# puente.net
KiCad netlist of a schematic drawn in EAGLE
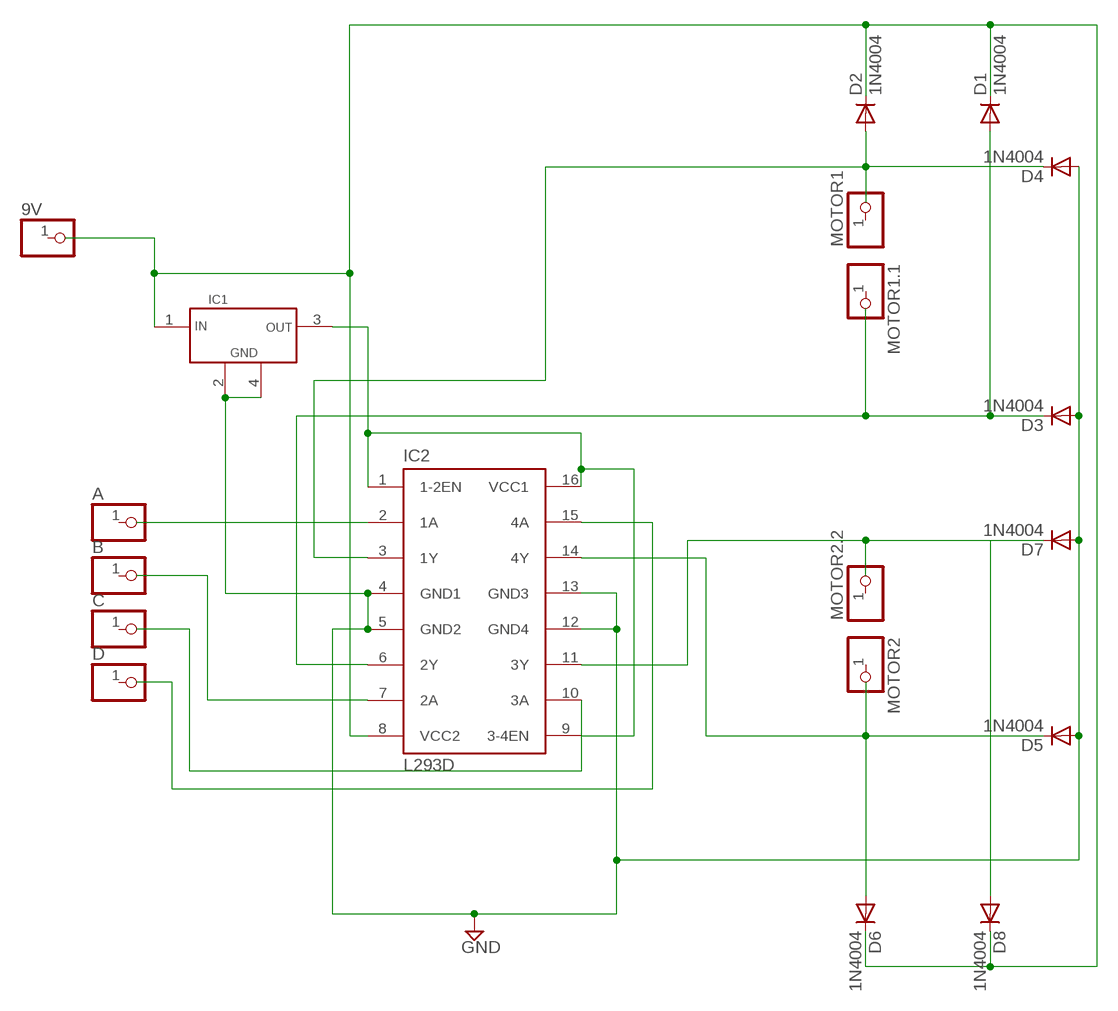
[diagram p0: schematic, sheet 1]

(export (version "E")
  (design (tool "Eeschema 10.0.6"))
  (components
    (comp (ref "9V")
      (value "PINHD-1X1")
      (footprint "eagle-import:1X01")
      (libsource (lib "eagle-import") (part "PINHD-1X1"))
    )
    (comp (ref "A")
      (value "PINHD-1X1")
      (footprint "eagle-import:1X01")
      (libsource (lib "eagle-import") (part "PINHD-1X1"))
    )
    (comp (ref "B")
      (value "PINHD-1X1")
      (footprint "eagle-import:1X01")
      (libsource (lib "eagle-import") (part "PINHD-1X1"))
    )
    (comp (ref "C")
      (value "PINHD-1X1")
      (footprint "eagle-import:1X01")
      (libsource (lib "eagle-import") (part "PINHD-1X1"))
    )
    (comp (ref "D")
      (value "PINHD-1X1")
      (footprint "eagle-import:1X01")
      (libsource (lib "eagle-import") (part "PINHD-1X1"))
    )
    (comp (ref "D1")
      (value "1N4004")
      (footprint "eagle-import:DO41-10")
      (libsource (lib "eagle-import") (part "1N4004"))
    )
    (comp (ref "D2")
      (value "1N4004")
      (footprint "eagle-import:DO41-10")
      (libsource (lib "eagle-import") (part "1N4004"))
    )
    (comp (ref "D3")
      (value "1N4004")
      (footprint "eagle-import:DO41-10")
      (libsource (lib "eagle-import") (part "1N4004"))
    )
    (comp (ref "D4")
      (value "1N4004")
      (footprint "eagle-import:DO41-10")
      (libsource (lib "eagle-import") (part "1N4004"))
    )
    (comp (ref "D5")
      (value "1N4004")
      (footprint "eagle-import:DO41-10")
      (libsource (lib "eagle-import") (part "1N4004"))
    )
    (comp (ref "D6")
      (value "1N4004")
      (footprint "eagle-import:DO41-10")
      (libsource (lib "eagle-import") (part "1N4004"))
    )
    (comp (ref "D7")
      (value "1N4004")
      (footprint "eagle-import:DO41-10")
      (libsource (lib "eagle-import") (part "1N4004"))
    )
    (comp (ref "D8")
      (value "1N4004")
      (footprint "eagle-import:DO41-10")
      (libsource (lib "eagle-import") (part "1N4004"))
    )
    (comp (ref "IC1")
      (value "7805")
      (footprint "eagle-import:SOT223")
      (libsource (lib "eagle-import") (part "7805"))
    )
    (comp (ref "IC2")
      (value "L293D")
      (footprint "eagle-import:DIL16")
      (libsource (lib "eagle-import") (part "L293D"))
    )
    (comp (ref "MOTOR1")
      (value "PINHD-1X1")
      (footprint "eagle-import:1X01")
      (libsource (lib "eagle-import") (part "PINHD-1X1"))
    )
    (comp (ref "MOTOR1.1")
      (value "PINHD-1X1")
      (footprint "eagle-import:1X01")
      (libsource (lib "eagle-import") (part "PINHD-1X1"))
    )
    (comp (ref "MOTOR2")
      (value "PINHD-1X1")
      (footprint "eagle-import:1X01")
      (libsource (lib "eagle-import") (part "PINHD-1X1"))
    )
    (comp (ref "MOTOR2.2")
      (value "PINHD-1X1")
      (footprint "eagle-import:1X01")
      (libsource (lib "eagle-import") (part "PINHD-1X1"))
    )
  )
  (nets
    (net (code "1") (name "GND") (class "Default")
      (node (ref "D3") (pin "A") (pinfunction "A_A") (pintype "passive"))
      (node (ref "D4") (pin "A") (pinfunction "A_A") (pintype "passive"))
      (node (ref "D5") (pin "A") (pinfunction "A_A") (pintype "passive"))
      (node (ref "D7") (pin "A") (pinfunction "A_A") (pintype "passive"))
      (node (ref "IC1") (pin "2") (pinfunction "GND_2") (pintype "bidirectional"))
      (node (ref "IC1") (pin "4") (pinfunction "GND_4") (pintype "bidirectional"))
      (node (ref "IC2") (pin "12") (pinfunction "GND4_12") (pintype "power_in"))
      (node (ref "IC2") (pin "13") (pinfunction "GND3_13") (pintype "power_in"))
      (node (ref "IC2") (pin "4") (pinfunction "GND1_4") (pintype "power_in"))
      (node (ref "IC2") (pin "5") (pinfunction "GND2_5") (pintype "power_in"))
    )
    (net (code "2") (name "Net-(IC1-IN)") (class "Default")
      (node (ref "D1") (pin "C") (pinfunction "C_C") (pintype "passive"))
      (node (ref "D2") (pin "C") (pinfunction "C_C") (pintype "passive"))
      (node (ref "D6") (pin "C") (pinfunction "C_C") (pintype "passive"))
      (node (ref "D8") (pin "C") (pinfunction "C_C") (pintype "passive"))
      (node (ref "IC1") (pin "1") (pinfunction "IN_1") (pintype "bidirectional"))
      (node (ref "IC2") (pin "8") (pinfunction "VCC2_8") (pintype "power_in"))
    )
    (net (code "3") (name "Net-(IC1-OUT)") (class "Default")
      (node (ref "IC1") (pin "3") (pinfunction "OUT_3") (pintype "bidirectional"))
      (node (ref "IC2") (pin "1") (pinfunction "1-2EN_1") (pintype "input"))
      (node (ref "IC2") (pin "16") (pinfunction "VCC1_16") (pintype "power_in"))
      (node (ref "IC2") (pin "9") (pinfunction "3-4EN_9") (pintype "input"))
    )
    (net (code "4") (name "Net-(IC2-1Y)") (class "Default")
      (node (ref "D2") (pin "A") (pinfunction "A_A") (pintype "passive"))
      (node (ref "D4") (pin "C") (pinfunction "C_C") (pintype "passive"))
      (node (ref "IC2") (pin "3") (pinfunction "1Y_3") (pintype "output"))
    )
    (net (code "5") (name "Net-(IC2-2Y)") (class "Default")
      (node (ref "D1") (pin "A") (pinfunction "A_A") (pintype "passive"))
      (node (ref "D3") (pin "C") (pinfunction "C_C") (pintype "passive"))
      (node (ref "IC2") (pin "6") (pinfunction "2Y_6") (pintype "output"))
    )
    (net (code "6") (name "Net-(IC2-3Y)") (class "Default")
      (node (ref "D7") (pin "C") (pinfunction "C_C") (pintype "passive"))
      (node (ref "D8") (pin "A") (pinfunction "A_A") (pintype "passive"))
      (node (ref "IC2") (pin "11") (pinfunction "3Y_11") (pintype "output"))
    )
    (net (code "7") (name "Net-(IC2-4Y)") (class "Default")
      (node (ref "D5") (pin "C") (pinfunction "C_C") (pintype "passive"))
      (node (ref "D6") (pin "A") (pinfunction "A_A") (pintype "passive"))
      (node (ref "IC2") (pin "14") (pinfunction "4Y_14") (pintype "output"))
    )
    (net (code "8") (name "unconnected-(9V-Pad1)") (class "Default")
      (node (ref "9V") (pin "1") (pinfunction "1_1") (pintype "passive"))
    )
    (net (code "9") (name "unconnected-(A-Pad1)") (class "Default")
      (node (ref "A") (pin "1") (pinfunction "1_1") (pintype "passive"))
    )
    (net (code "10") (name "unconnected-(B-Pad1)") (class "Default")
      (node (ref "B") (pin "1") (pinfunction "1_1") (pintype "passive"))
    )
    (net (code "11") (name "unconnected-(C-Pad1)") (class "Default")
      (node (ref "C") (pin "1") (pinfunction "1_1") (pintype "passive"))
    )
    (net (code "12") (name "unconnected-(D-Pad1)") (class "Default")
      (node (ref "D") (pin "1") (pinfunction "1_1") (pintype "passive"))
    )
    (net (code "13") (name "unconnected-(IC2-1A-Pad2)") (class "Default")
      (node (ref "IC2") (pin "2") (pinfunction "1A_2") (pintype "input"))
    )
    (net (code "14") (name "unconnected-(IC2-2A-Pad7)") (class "Default")
      (node (ref "IC2") (pin "7") (pinfunction "2A_7") (pintype "input"))
    )
    (net (code "15") (name "unconnected-(IC2-3A-Pad10)") (class "Default")
      (node (ref "IC2") (pin "10") (pinfunction "3A_10") (pintype "input"))
    )
    (net (code "16") (name "unconnected-(IC2-4A-Pad15)") (class "Default")
      (node (ref "IC2") (pin "15") (pinfunction "4A_15") (pintype "input"))
    )
    (net (code "17") (name "unconnected-(MOTOR1-Pad1)") (class "Default")
      (node (ref "MOTOR1") (pin "1") (pinfunction "1_1") (pintype "passive"))
    )
    (net (code "18") (name "unconnected-(MOTOR1.1-Pad1)") (class "Default")
      (node (ref "MOTOR1.1") (pin "1") (pinfunction "1_1") (pintype "passive"))
    )
    (net (code "19") (name "unconnected-(MOTOR2-Pad1)") (class "Default")
      (node (ref "MOTOR2") (pin "1") (pinfunction "1_1") (pintype "passive"))
    )
    (net (code "20") (name "unconnected-(MOTOR2.2-Pad1)") (class "Default")
      (node (ref "MOTOR2.2") (pin "1") (pinfunction "1_1") (pintype "passive"))
    )
  )
)
